# ArduinoWriter.net
KiCad netlist of a schematic drawn in EAGLE
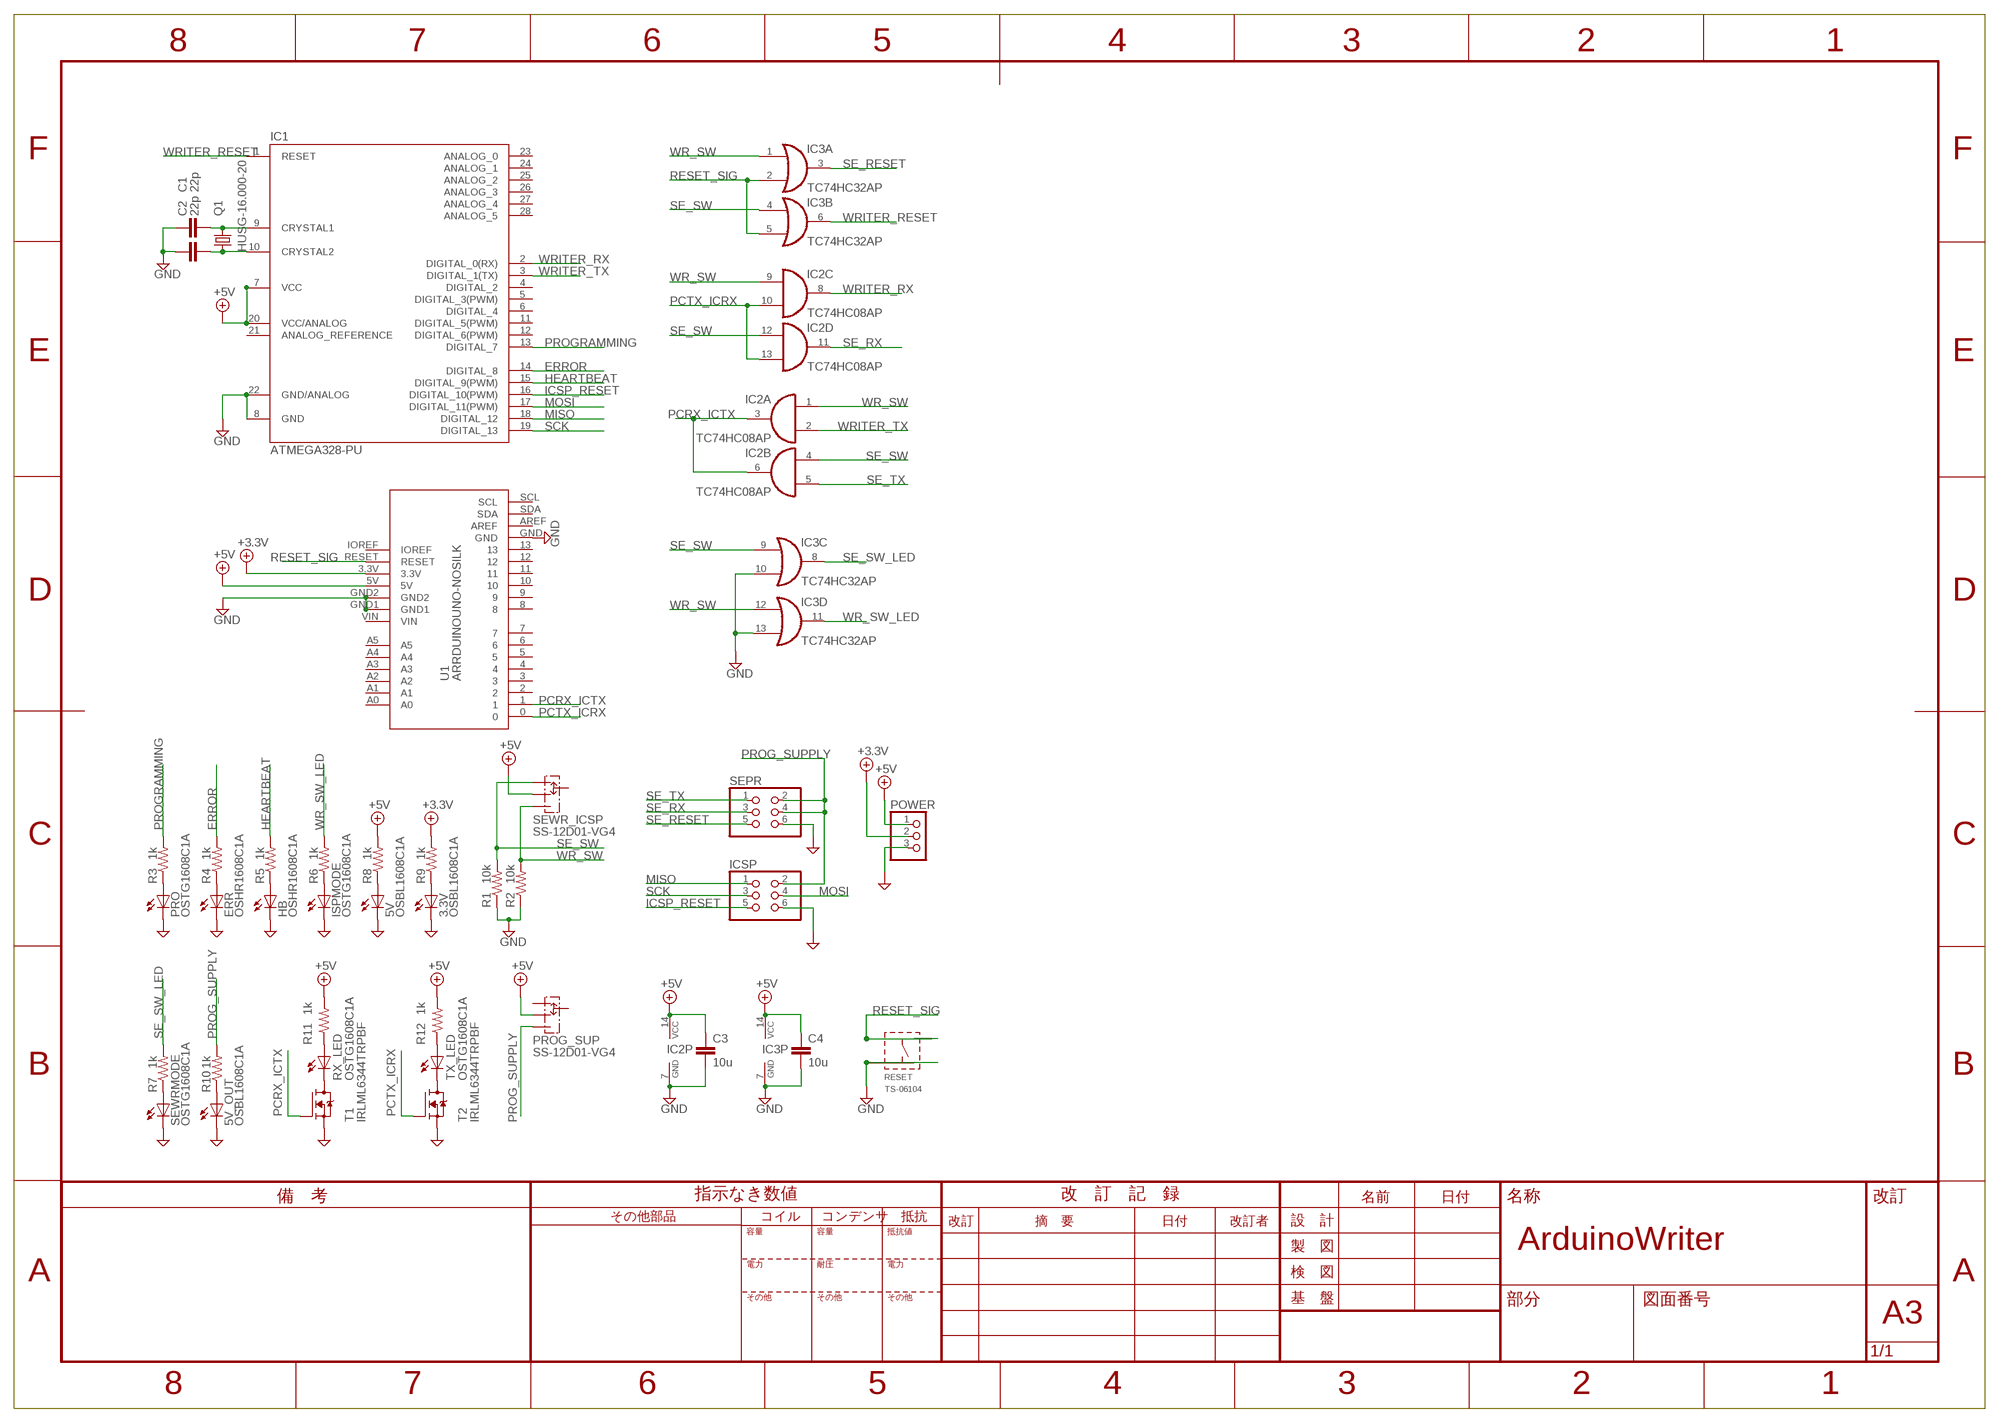
[diagram p0: schematic, sheet 1]

(export (version "E")
  (design (tool "Eeschema 10.0.6"))
  (components
    (comp (ref "3.3V")
      (value "OSBL1608C1A")
      (footprint "eagle-import:LEDC1608X39N_B")
      (libsource (lib "eagle-import") (part "OSBL1608C1A"))
    )
    (comp (ref "5V")
      (value "OSBL1608C1A")
      (footprint "eagle-import:LEDC1608X39N_B")
      (libsource (lib "eagle-import") (part "OSBL1608C1A"))
    )
    (comp (ref "5V_OUT")
      (value "OSBL1608C1A")
      (footprint "eagle-import:LEDC1608X39N_B")
      (libsource (lib "eagle-import") (part "OSBL1608C1A"))
    )
    (comp (ref "C1")
      (value "22p")
      (footprint "eagle-import:C0603")
      (libsource (lib "eagle-import") (part "C1608"))
    )
    (comp (ref "C2")
      (value "22p")
      (footprint "eagle-import:C0603")
      (libsource (lib "eagle-import") (part "C1608"))
    )
    (comp (ref "C3")
      (value "10u")
      (footprint "eagle-import:C0805")
      (libsource (lib "eagle-import") (part "C2012"))
    )
    (comp (ref "C4")
      (value "10u")
      (footprint "eagle-import:C0805")
      (libsource (lib "eagle-import") (part "C2012"))
    )
    (comp (ref "ERR")
      (value "OSHR1608C1A")
      (footprint "eagle-import:LEDC1608X39N_R")
      (libsource (lib "eagle-import") (part "OSHR1608C1A"))
    )
    (comp (ref "HB")
      (value "OSHR1608C1A")
      (footprint "eagle-import:LEDC1608X39N_R")
      (libsource (lib "eagle-import") (part "OSHR1608C1A"))
    )
    (comp (ref "IC1")
      (value "ATMEGA328-PU")
      (footprint "eagle-import:DIL28-3")
      (libsource (lib "eagle-import") (part "ATMEGA328-PU"))
    )
    (comp (ref "IC2")
      (value "TC74HC08AP")
      (footprint "eagle-import:DIL14")
      (libsource (lib "eagle-import") (part "TC74HC08AP"))
    )
    (comp (ref "IC3")
      (value "TC74HC32AP")
      (footprint "eagle-import:DIL14")
      (libsource (lib "eagle-import") (part "TC74HC32AP"))
    )
    (comp (ref "ICSP")
      (value "PINHD-2X3/90")
      (footprint "eagle-import:2X03_90")
      (libsource (lib "eagle-import") (part "PINHD-2X3/90"))
    )
    (comp (ref "ISPMODE")
      (value "OSTG1608C1A")
      (footprint "eagle-import:LEDC1608X39N_G")
      (libsource (lib "eagle-import") (part "OSTG1608C1A"))
    )
    (comp (ref "POWER")
      (value "PINHD-1X3")
      (footprint "eagle-import:1X03")
      (libsource (lib "eagle-import") (part "PINHD-1X3"))
    )
    (comp (ref "PRO")
      (value "OSTG1608C1A")
      (footprint "eagle-import:LEDC1608X39N_G")
      (libsource (lib "eagle-import") (part "OSTG1608C1A"))
    )
    (comp (ref "PROG_SUP")
      (value "SS-12D01-VG4")
      (footprint "eagle-import:SS-12D01-VG4")
      (libsource (lib "eagle-import") (part "SS-12D01-VG4"))
    )
    (comp (ref "Q1")
      (value "HUSG-16.000-20")
      (footprint "eagle-import:XTALRR480W50L990T368H350B")
      (libsource (lib "eagle-import") (part "HUSG-16.000-20"))
    )
    (comp (ref "R1")
      (value "10k")
      (footprint "eagle-import:R0603")
      (libsource (lib "eagle-import") (part "R1608"))
    )
    (comp (ref "R2")
      (value "10k")
      (footprint "eagle-import:R0603")
      (libsource (lib "eagle-import") (part "R1608"))
    )
    (comp (ref "R3")
      (value "1k")
      (footprint "eagle-import:R0603")
      (libsource (lib "eagle-import") (part "R1608"))
    )
    (comp (ref "R4")
      (value "1k")
      (footprint "eagle-import:R0603")
      (libsource (lib "eagle-import") (part "R1608"))
    )
    (comp (ref "R5")
      (value "1k")
      (footprint "eagle-import:R0603")
      (libsource (lib "eagle-import") (part "R1608"))
    )
    (comp (ref "R6")
      (value "1k")
      (footprint "eagle-import:R0603")
      (libsource (lib "eagle-import") (part "R1608"))
    )
    (comp (ref "R7")
      (value "1k")
      (footprint "eagle-import:R0603")
      (libsource (lib "eagle-import") (part "R1608"))
    )
    (comp (ref "R8")
      (value "1k")
      (footprint "eagle-import:R0603")
      (libsource (lib "eagle-import") (part "R1608"))
    )
    (comp (ref "R9")
      (value "1k")
      (footprint "eagle-import:R0603")
      (libsource (lib "eagle-import") (part "R1608"))
    )
    (comp (ref "R10")
      (value "1k")
      (footprint "eagle-import:R0603")
      (libsource (lib "eagle-import") (part "R1608"))
    )
    (comp (ref "R11")
      (value "1k")
      (footprint "eagle-import:R0603")
      (libsource (lib "eagle-import") (part "R1608"))
    )
    (comp (ref "R12")
      (value "1k")
      (footprint "eagle-import:R0603")
      (libsource (lib "eagle-import") (part "R1608"))
    )
    (comp (ref "RESET")
      (value "TS-06104")
      (footprint "eagle-import:TS-06104")
      (libsource (lib "eagle-import") (part "TS-06104"))
    )
    (comp (ref "RX_LED")
      (value "OSTG1608C1A")
      (footprint "eagle-import:LEDC1608X39N_G")
      (libsource (lib "eagle-import") (part "OSTG1608C1A"))
    )
    (comp (ref "SEPR")
      (value "PINHD-2X3/90")
      (footprint "eagle-import:2X03_90")
      (libsource (lib "eagle-import") (part "PINHD-2X3/90"))
    )
    (comp (ref "SEWRMODE")
      (value "OSTG1608C1A")
      (footprint "eagle-import:LEDC1608X39N_G")
      (libsource (lib "eagle-import") (part "OSTG1608C1A"))
    )
    (comp (ref "SEWR_ICSP")
      (value "SS-12D01-VG4")
      (footprint "eagle-import:SS-12D01-VG4")
      (libsource (lib "eagle-import") (part "SS-12D01-VG4"))
    )
    (comp (ref "T1")
      (value "IRLML6344TRPBF")
      (footprint "eagle-import:SOT95P240X110-3N")
      (libsource (lib "eagle-import") (part "IRLML6344TRPBF"))
    )
    (comp (ref "T2")
      (value "IRLML6344TRPBF")
      (footprint "eagle-import:SOT95P240X110-3N")
      (libsource (lib "eagle-import") (part "IRLML6344TRPBF"))
    )
    (comp (ref "TX_LED")
      (value "OSTG1608C1A")
      (footprint "eagle-import:LEDC1608X39N_G")
      (libsource (lib "eagle-import") (part "OSTG1608C1A"))
    )
    (comp (ref "U1")
      (value "ARRDUINOUNO-NOSILK")
      (footprint "eagle-import:ARDUINOUNO_NOSILK")
      (libsource (lib "eagle-import") (part "ARRDUINOUNO-NOSILK"))
    )
  )
  (nets
    (net (code "1") (name "+3.3V") (class "Default")
      (node (ref "POWER") (pin "2") (pinfunction "2_2") (pintype "passive"))
      (node (ref "R9") (pin "2") (pinfunction "2_2") (pintype "passive"))
      (node (ref "U1") (pin "3.3V") (pinfunction "3.3V_3.3V") (pintype "bidirectional"))
    )
    (net (code "2") (name "+5V") (class "Default")
      (node (ref "C3") (pin "1") (pinfunction "1_1") (pintype "passive"))
      (node (ref "C4") (pin "1") (pinfunction "1_1") (pintype "passive"))
      (node (ref "IC1") (pin "20") (pinfunction "VCC/ANALOG_20") (pintype "passive"))
      (node (ref "IC1") (pin "7") (pinfunction "VCC_7") (pintype "power_in"))
      (node (ref "IC2") (pin "14") (pinfunction "VCC_14") (pintype "power_in"))
      (node (ref "IC3") (pin "14") (pinfunction "VCC_14") (pintype "power_in"))
      (node (ref "POWER") (pin "1") (pinfunction "1_1") (pintype "passive"))
      (node (ref "PROG_SUP") (pin "COM") (pinfunction "COM_COM") (pintype "bidirectional"))
      (node (ref "R11") (pin "2") (pinfunction "2_2") (pintype "passive"))
      (node (ref "R12") (pin "2") (pinfunction "2_2") (pintype "passive"))
      (node (ref "R8") (pin "2") (pinfunction "2_2") (pintype "passive"))
      (node (ref "SEWR_ICSP") (pin "COM") (pinfunction "COM_COM") (pintype "bidirectional"))
      (node (ref "U1") (pin "5V") (pinfunction "5V_5V") (pintype "bidirectional"))
    )
    (net (code "3") (name "/ERROR") (class "Default")
      (node (ref "IC1") (pin "14") (pinfunction "DIGITAL_8_14") (pintype "bidirectional"))
      (node (ref "R4") (pin "2") (pinfunction "2_2") (pintype "passive"))
    )
    (net (code "4") (name "/HEARTBEAT") (class "Default")
      (node (ref "IC1") (pin "15") (pinfunction "DIGITAL_9(PWM)_15") (pintype "bidirectional"))
      (node (ref "R5") (pin "2") (pinfunction "2_2") (pintype "passive"))
    )
    (net (code "5") (name "/ICSP_RESET") (class "Default")
      (node (ref "IC1") (pin "16") (pinfunction "DIGITAL_10(PWM)_16") (pintype "bidirectional"))
      (node (ref "ICSP") (pin "5") (pinfunction "5_5") (pintype "passive"))
    )
    (net (code "6") (name "/MISO") (class "Default")
      (node (ref "IC1") (pin "18") (pinfunction "DIGITAL_12_18") (pintype "bidirectional"))
      (node (ref "ICSP") (pin "1") (pinfunction "1_1") (pintype "passive"))
    )
    (net (code "7") (name "/MOSI") (class "Default")
      (node (ref "IC1") (pin "17") (pinfunction "DIGITAL_11(PWM)_17") (pintype "bidirectional"))
      (node (ref "ICSP") (pin "4") (pinfunction "4_4") (pintype "passive"))
    )
    (net (code "8") (name "/PCRX_ICTX") (class "Default")
      (node (ref "IC2") (pin "3") (pinfunction "O_3") (pintype "output"))
      (node (ref "IC2") (pin "6") (pinfunction "O_6") (pintype "output"))
      (node (ref "T1") (pin "1") (pinfunction "G_1") (pintype "passive"))
      (node (ref "U1") (pin "1") (pinfunction "1_1") (pintype "bidirectional"))
    )
    (net (code "9") (name "/PCTX_ICRX") (class "Default")
      (node (ref "IC2") (pin "10") (pinfunction "I1_10") (pintype "input"))
      (node (ref "IC2") (pin "13") (pinfunction "I1_13") (pintype "input"))
      (node (ref "T2") (pin "1") (pinfunction "G_1") (pintype "passive"))
      (node (ref "U1") (pin "0") (pinfunction "0_0") (pintype "bidirectional"))
    )
    (net (code "10") (name "/PROGRAMMING") (class "Default")
      (node (ref "IC1") (pin "13") (pinfunction "DIGITAL_7_13") (pintype "bidirectional"))
      (node (ref "R3") (pin "2") (pinfunction "2_2") (pintype "passive"))
    )
    (net (code "11") (name "/PROG_SUPPLY") (class "Default")
      (node (ref "ICSP") (pin "2") (pinfunction "2_2") (pintype "passive"))
      (node (ref "PROG_SUP") (pin "NO") (pinfunction "NO_NO") (pintype "bidirectional"))
      (node (ref "R10") (pin "2") (pinfunction "2_2") (pintype "passive"))
      (node (ref "SEPR") (pin "2") (pinfunction "2_2") (pintype "passive"))
      (node (ref "SEPR") (pin "4") (pinfunction "4_4") (pintype "passive"))
    )
    (net (code "12") (name "/RESET_SIG") (class "Default")
      (node (ref "IC3") (pin "2") (pinfunction "I1_2") (pintype "input"))
      (node (ref "IC3") (pin "5") (pinfunction "I1_5") (pintype "input"))
      (node (ref "RESET") (pin "A1") (pinfunction "T1_A1") (pintype "bidirectional"))
      (node (ref "RESET") (pin "A2") (pinfunction "T2_A2") (pintype "bidirectional"))
      (node (ref "U1") (pin "RESET") (pinfunction "RESET_RESET") (pintype "bidirectional"))
    )
    (net (code "13") (name "/SCK") (class "Default")
      (node (ref "IC1") (pin "19") (pinfunction "DIGITAL_13_19") (pintype "bidirectional"))
      (node (ref "ICSP") (pin "3") (pinfunction "3_3") (pintype "passive"))
    )
    (net (code "14") (name "/SE_RESET") (class "Default")
      (node (ref "IC3") (pin "3") (pinfunction "O_3") (pintype "output"))
      (node (ref "SEPR") (pin "5") (pinfunction "5_5") (pintype "passive"))
    )
    (net (code "15") (name "/SE_RX") (class "Default")
      (node (ref "IC2") (pin "11") (pinfunction "O_11") (pintype "output"))
      (node (ref "SEPR") (pin "3") (pinfunction "3_3") (pintype "passive"))
    )
    (net (code "16") (name "/SE_SW") (class "Default")
      (node (ref "IC2") (pin "12") (pinfunction "I0_12") (pintype "input"))
      (node (ref "IC2") (pin "4") (pinfunction "I0_4") (pintype "input"))
      (node (ref "IC3") (pin "4") (pinfunction "I0_4") (pintype "input"))
      (node (ref "IC3") (pin "9") (pinfunction "I0_9") (pintype "input"))
      (node (ref "R1") (pin "2") (pinfunction "2_2") (pintype "passive"))
      (node (ref "SEWR_ICSP") (pin "NC") (pinfunction "NC_NC") (pintype "bidirectional"))
    )
    (net (code "17") (name "/SE_SW_LED") (class "Default")
      (node (ref "IC3") (pin "8") (pinfunction "O_8") (pintype "output"))
      (node (ref "R7") (pin "2") (pinfunction "2_2") (pintype "passive"))
    )
    (net (code "18") (name "/SE_TX") (class "Default")
      (node (ref "IC2") (pin "5") (pinfunction "I1_5") (pintype "input"))
      (node (ref "SEPR") (pin "1") (pinfunction "1_1") (pintype "passive"))
    )
    (net (code "19") (name "/WRITER_RESET") (class "Default")
      (node (ref "IC1") (pin "1") (pinfunction "RESET_1") (pintype "bidirectional"))
      (node (ref "IC3") (pin "6") (pinfunction "O_6") (pintype "output"))
    )
    (net (code "20") (name "/WRITER_RX") (class "Default")
      (node (ref "IC1") (pin "2") (pinfunction "DIGITAL_0(RX)_2") (pintype "bidirectional"))
      (node (ref "IC2") (pin "8") (pinfunction "O_8") (pintype "output"))
    )
    (net (code "21") (name "/WRITER_TX") (class "Default")
      (node (ref "IC1") (pin "3") (pinfunction "DIGITAL_1(TX)_3") (pintype "bidirectional"))
      (node (ref "IC2") (pin "2") (pinfunction "I1_2") (pintype "input"))
    )
    (net (code "22") (name "/WR_SW") (class "Default")
      (node (ref "IC2") (pin "1") (pinfunction "I0_1") (pintype "input"))
      (node (ref "IC2") (pin "9") (pinfunction "I0_9") (pintype "input"))
      (node (ref "IC3") (pin "1") (pinfunction "I0_1") (pintype "input"))
      (node (ref "IC3") (pin "12") (pinfunction "I0_12") (pintype "input"))
      (node (ref "R2") (pin "2") (pinfunction "2_2") (pintype "passive"))
      (node (ref "SEWR_ICSP") (pin "NO") (pinfunction "NO_NO") (pintype "bidirectional"))
    )
    (net (code "23") (name "/WR_SW_LED") (class "Default")
      (node (ref "IC3") (pin "11") (pinfunction "O_11") (pintype "output"))
      (node (ref "R6") (pin "2") (pinfunction "2_2") (pintype "passive"))
    )
    (net (code "24") (name "GND") (class "Default")
      (node (ref "3.3V") (pin "2") (pinfunction "C_2") (pintype "passive"))
      (node (ref "5V") (pin "2") (pinfunction "C_2") (pintype "passive"))
      (node (ref "5V_OUT") (pin "2") (pinfunction "C_2") (pintype "passive"))
      (node (ref "C1") (pin "1") (pinfunction "1_1") (pintype "passive"))
      (node (ref "C2") (pin "1") (pinfunction "1_1") (pintype "passive"))
      (node (ref "C3") (pin "2") (pinfunction "2_2") (pintype "passive"))
      (node (ref "C4") (pin "2") (pinfunction "2_2") (pintype "passive"))
      (node (ref "ERR") (pin "2") (pinfunction "C_2") (pintype "passive"))
      (node (ref "HB") (pin "2") (pinfunction "C_2") (pintype "passive"))
      (node (ref "IC1") (pin "22") (pinfunction "GND/ANALOG_22") (pintype "power_in"))
      (node (ref "IC1") (pin "8") (pinfunction "GND_8") (pintype "power_in"))
      (node (ref "IC2") (pin "7") (pinfunction "GND_7") (pintype "power_in"))
      (node (ref "IC3") (pin "10") (pinfunction "I1_10") (pintype "input"))
      (node (ref "IC3") (pin "13") (pinfunction "I1_13") (pintype "input"))
      (node (ref "IC3") (pin "7") (pinfunction "GND_7") (pintype "power_in"))
      (node (ref "ICSP") (pin "6") (pinfunction "6_6") (pintype "passive"))
      (node (ref "ISPMODE") (pin "K") (pinfunction "C_K") (pintype "passive"))
      (node (ref "POWER") (pin "3") (pinfunction "3_3") (pintype "passive"))
      (node (ref "PRO") (pin "K") (pinfunction "C_K") (pintype "passive"))
      (node (ref "R1") (pin "1") (pinfunction "1_1") (pintype "passive"))
      (node (ref "R2") (pin "1") (pinfunction "1_1") (pintype "passive"))
      (node (ref "RESET") (pin "B1") (pinfunction "T3_B1") (pintype "bidirectional"))
      (node (ref "RESET") (pin "B2") (pinfunction "T4_B2") (pintype "bidirectional"))
      (node (ref "SEPR") (pin "6") (pinfunction "6_6") (pintype "passive"))
      (node (ref "SEWRMODE") (pin "K") (pinfunction "C_K") (pintype "passive"))
      (node (ref "T1") (pin "2") (pinfunction "S_2") (pintype "passive"))
      (node (ref "T2") (pin "2") (pinfunction "S_2") (pintype "passive"))
      (node (ref "U1") (pin "GND") (pinfunction "GND_GND") (pintype "bidirectional"))
      (node (ref "U1") (pin "GND1") (pinfunction "GND1_GND1") (pintype "bidirectional"))
      (node (ref "U1") (pin "GND2") (pinfunction "GND2_GND2") (pintype "bidirectional"))
    )
    (net (code "25") (name "Net-(3.3V-A)") (class "Default")
      (node (ref "3.3V") (pin "1") (pinfunction "A_1") (pintype "passive"))
      (node (ref "R9") (pin "1") (pinfunction "1_1") (pintype "passive"))
    )
    (net (code "26") (name "Net-(5V-A)") (class "Default")
      (node (ref "5V") (pin "1") (pinfunction "A_1") (pintype "passive"))
      (node (ref "R8") (pin "1") (pinfunction "1_1") (pintype "passive"))
    )
    (net (code "27") (name "Net-(5V_OUT-A)") (class "Default")
      (node (ref "5V_OUT") (pin "1") (pinfunction "A_1") (pintype "passive"))
      (node (ref "R10") (pin "1") (pinfunction "1_1") (pintype "passive"))
    )
    (net (code "28") (name "Net-(ERR-A)") (class "Default")
      (node (ref "ERR") (pin "1") (pinfunction "A_1") (pintype "passive"))
      (node (ref "R4") (pin "1") (pinfunction "1_1") (pintype "passive"))
    )
    (net (code "29") (name "Net-(HB-A)") (class "Default")
      (node (ref "HB") (pin "1") (pinfunction "A_1") (pintype "passive"))
      (node (ref "R5") (pin "1") (pinfunction "1_1") (pintype "passive"))
    )
    (net (code "30") (name "Net-(IC1-CRYSTAL1)") (class "Default")
      (node (ref "C1") (pin "2") (pinfunction "2_2") (pintype "passive"))
      (node (ref "IC1") (pin "9") (pinfunction "CRYSTAL1_9") (pintype "bidirectional"))
      (node (ref "Q1") (pin "2") (pinfunction "2_2") (pintype "passive"))
    )
    (net (code "31") (name "Net-(IC1-CRYSTAL2)") (class "Default")
      (node (ref "C2") (pin "2") (pinfunction "2_2") (pintype "passive"))
      (node (ref "IC1") (pin "10") (pinfunction "CRYSTAL2_10") (pintype "bidirectional"))
      (node (ref "Q1") (pin "1") (pinfunction "1_1") (pintype "passive"))
    )
    (net (code "32") (name "Net-(ISPMODE-PadA)") (class "Default")
      (node (ref "ISPMODE") (pin "A") (pinfunction "A_A") (pintype "passive"))
      (node (ref "R6") (pin "1") (pinfunction "1_1") (pintype "passive"))
    )
    (net (code "33") (name "Net-(PRO-PadA)") (class "Default")
      (node (ref "PRO") (pin "A") (pinfunction "A_A") (pintype "passive"))
      (node (ref "R3") (pin "1") (pinfunction "1_1") (pintype "passive"))
    )
    (net (code "34") (name "Net-(R7-Pad1)") (class "Default")
      (node (ref "R7") (pin "1") (pinfunction "1_1") (pintype "passive"))
      (node (ref "SEWRMODE") (pin "A") (pinfunction "A_A") (pintype "passive"))
    )
    (net (code "35") (name "Net-(R11-Pad1)") (class "Default")
      (node (ref "R11") (pin "1") (pinfunction "1_1") (pintype "passive"))
      (node (ref "RX_LED") (pin "A") (pinfunction "A_A") (pintype "passive"))
    )
    (net (code "36") (name "Net-(R12-Pad1)") (class "Default")
      (node (ref "R12") (pin "1") (pinfunction "1_1") (pintype "passive"))
      (node (ref "TX_LED") (pin "A") (pinfunction "A_A") (pintype "passive"))
    )
    (net (code "37") (name "Net-(RX_LED-C)") (class "Default")
      (node (ref "RX_LED") (pin "K") (pinfunction "C_K") (pintype "passive"))
      (node (ref "T1") (pin "3") (pinfunction "D_3") (pintype "passive"))
    )
    (net (code "38") (name "Net-(T2-D)") (class "Default")
      (node (ref "T2") (pin "3") (pinfunction "D_3") (pintype "passive"))
      (node (ref "TX_LED") (pin "K") (pinfunction "C_K") (pintype "passive"))
    )
    (net (code "39") (name "unconnected-(IC1-ANALOG_0-Pad23)") (class "Default")
      (node (ref "IC1") (pin "23") (pinfunction "ANALOG_0_23") (pintype "bidirectional"))
    )
    (net (code "40") (name "unconnected-(IC1-ANALOG_1-Pad24)") (class "Default")
      (node (ref "IC1") (pin "24") (pinfunction "ANALOG_1_24") (pintype "bidirectional"))
    )
    (net (code "41") (name "unconnected-(IC1-ANALOG_2-Pad25)") (class "Default")
      (node (ref "IC1") (pin "25") (pinfunction "ANALOG_2_25") (pintype "bidirectional"))
    )
    (net (code "42") (name "unconnected-(IC1-ANALOG_3-Pad26)") (class "Default")
      (node (ref "IC1") (pin "26") (pinfunction "ANALOG_3_26") (pintype "bidirectional"))
    )
    (net (code "43") (name "unconnected-(IC1-ANALOG_4-Pad27)") (class "Default")
      (node (ref "IC1") (pin "27") (pinfunction "ANALOG_4_27") (pintype "bidirectional"))
    )
    (net (code "44") (name "unconnected-(IC1-ANALOG_5-Pad28)") (class "Default")
      (node (ref "IC1") (pin "28") (pinfunction "ANALOG_5_28") (pintype "bidirectional"))
    )
    (net (code "45") (name "unconnected-(IC1-ANALOG_REFERENCE-Pad21)") (class "Default")
      (node (ref "IC1") (pin "21") (pinfunction "ANALOG_REFERENCE_21") (pintype "passive"))
    )
    (net (code "46") (name "unconnected-(IC1-DIGITAL_2-Pad4)") (class "Default")
      (node (ref "IC1") (pin "4") (pinfunction "DIGITAL_2_4") (pintype "bidirectional"))
    )
    (net (code "47") (name "unconnected-(IC1-DIGITAL_3(PWM)-Pad5)") (class "Default")
      (node (ref "IC1") (pin "5") (pinfunction "DIGITAL_3(PWM)_5") (pintype "bidirectional"))
    )
    (net (code "48") (name "unconnected-(IC1-DIGITAL_4-Pad6)") (class "Default")
      (node (ref "IC1") (pin "6") (pinfunction "DIGITAL_4_6") (pintype "bidirectional"))
    )
    (net (code "49") (name "unconnected-(IC1-DIGITAL_5(PWM)-Pad11)") (class "Default")
      (node (ref "IC1") (pin "11") (pinfunction "DIGITAL_5(PWM)_11") (pintype "bidirectional"))
    )
    (net (code "50") (name "unconnected-(IC1-DIGITAL_6(PWM)-Pad12)") (class "Default")
      (node (ref "IC1") (pin "12") (pinfunction "DIGITAL_6(PWM)_12") (pintype "bidirectional"))
    )
    (net (code "51") (name "unconnected-(PROG_SUP-PadNC)") (class "Default")
      (node (ref "PROG_SUP") (pin "NC") (pinfunction "NC_NC") (pintype "bidirectional"))
    )
    (net (code "52") (name "unconnected-(U1-Pad2)") (class "Default")
      (node (ref "U1") (pin "2") (pinfunction "2_2") (pintype "bidirectional"))
    )
    (net (code "53") (name "unconnected-(U1-Pad3)") (class "Default")
      (node (ref "U1") (pin "3") (pinfunction "3_3") (pintype "bidirectional"))
    )
    (net (code "54") (name "unconnected-(U1-Pad4)") (class "Default")
      (node (ref "U1") (pin "4") (pinfunction "4_4") (pintype "bidirectional"))
    )
    (net (code "55") (name "unconnected-(U1-Pad5)") (class "Default")
      (node (ref "U1") (pin "5") (pinfunction "5_5") (pintype "bidirectional"))
    )
    (net (code "56") (name "unconnected-(U1-Pad6)") (class "Default")
      (node (ref "U1") (pin "6") (pinfunction "6_6") (pintype "bidirectional"))
    )
    (net (code "57") (name "unconnected-(U1-Pad7)") (class "Default")
      (node (ref "U1") (pin "7") (pinfunction "7_7") (pintype "bidirectional"))
    )
    (net (code "58") (name "unconnected-(U1-Pad8)") (class "Default")
      (node (ref "U1") (pin "8") (pinfunction "8_8") (pintype "bidirectional"))
    )
    (net (code "59") (name "unconnected-(U1-Pad9)") (class "Default")
      (node (ref "U1") (pin "9") (pinfunction "9_9") (pintype "bidirectional"))
    )
    (net (code "60") (name "unconnected-(U1-Pad10)") (class "Default")
      (node (ref "U1") (pin "10") (pinfunction "10_10") (pintype "bidirectional"))
    )
    (net (code "61") (name "unconnected-(U1-Pad11)") (class "Default")
      (node (ref "U1") (pin "11") (pinfunction "11_11") (pintype "bidirectional"))
    )
    (net (code "62") (name "unconnected-(U1-Pad12)") (class "Default")
      (node (ref "U1") (pin "12") (pinfunction "12_12") (pintype "bidirectional"))
    )
    (net (code "63") (name "unconnected-(U1-Pad13)") (class "Default")
      (node (ref "U1") (pin "13") (pinfunction "13_13") (pintype "bidirectional"))
    )
    (net (code "64") (name "unconnected-(U1-PadA0)") (class "Default")
      (node (ref "U1") (pin "A0") (pinfunction "A0_A0") (pintype "bidirectional"))
    )
    (net (code "65") (name "unconnected-(U1-PadA1)") (class "Default")
      (node (ref "U1") (pin "A1") (pinfunction "A1_A1") (pintype "bidirectional"))
    )
    (net (code "66") (name "unconnected-(U1-PadA2)") (class "Default")
      (node (ref "U1") (pin "A2") (pinfunction "A2_A2") (pintype "bidirectional"))
    )
    (net (code "67") (name "unconnected-(U1-PadA3)") (class "Default")
      (node (ref "U1") (pin "A3") (pinfunction "A3_A3") (pintype "bidirectional"))
    )
    (net (code "68") (name "unconnected-(U1-PadA4)") (class "Default")
      (node (ref "U1") (pin "A4") (pinfunction "A4_A4") (pintype "bidirectional"))
    )
    (net (code "69") (name "unconnected-(U1-PadA5)") (class "Default")
      (node (ref "U1") (pin "A5") (pinfunction "A5_A5") (pintype "bidirectional"))
    )
    (net (code "70") (name "unconnected-(U1-PadAREF)") (class "Default")
      (node (ref "U1") (pin "AREF") (pinfunction "AREF_AREF") (pintype "bidirectional"))
    )
    (net (code "71") (name "unconnected-(U1-PadIOREF)") (class "Default")
      (node (ref "U1") (pin "IOREF") (pinfunction "IOREF_IOREF") (pintype "bidirectional"))
    )
    (net (code "72") (name "unconnected-(U1-PadSCL)") (class "Default")
      (node (ref "U1") (pin "SCL") (pinfunction "SCL_SCL") (pintype "bidirectional"))
    )
    (net (code "73") (name "unconnected-(U1-PadSDA)") (class "Default")
      (node (ref "U1") (pin "SDA") (pinfunction "SDA_SDA") (pintype "bidirectional"))
    )
    (net (code "74") (name "unconnected-(U1-PadVIN)") (class "Default")
      (node (ref "U1") (pin "VIN") (pinfunction "VIN_VIN") (pintype "bidirectional"))
    )
  )
)
